# Adafruit_BMP180.net
KiCad netlist of a schematic drawn in EAGLE
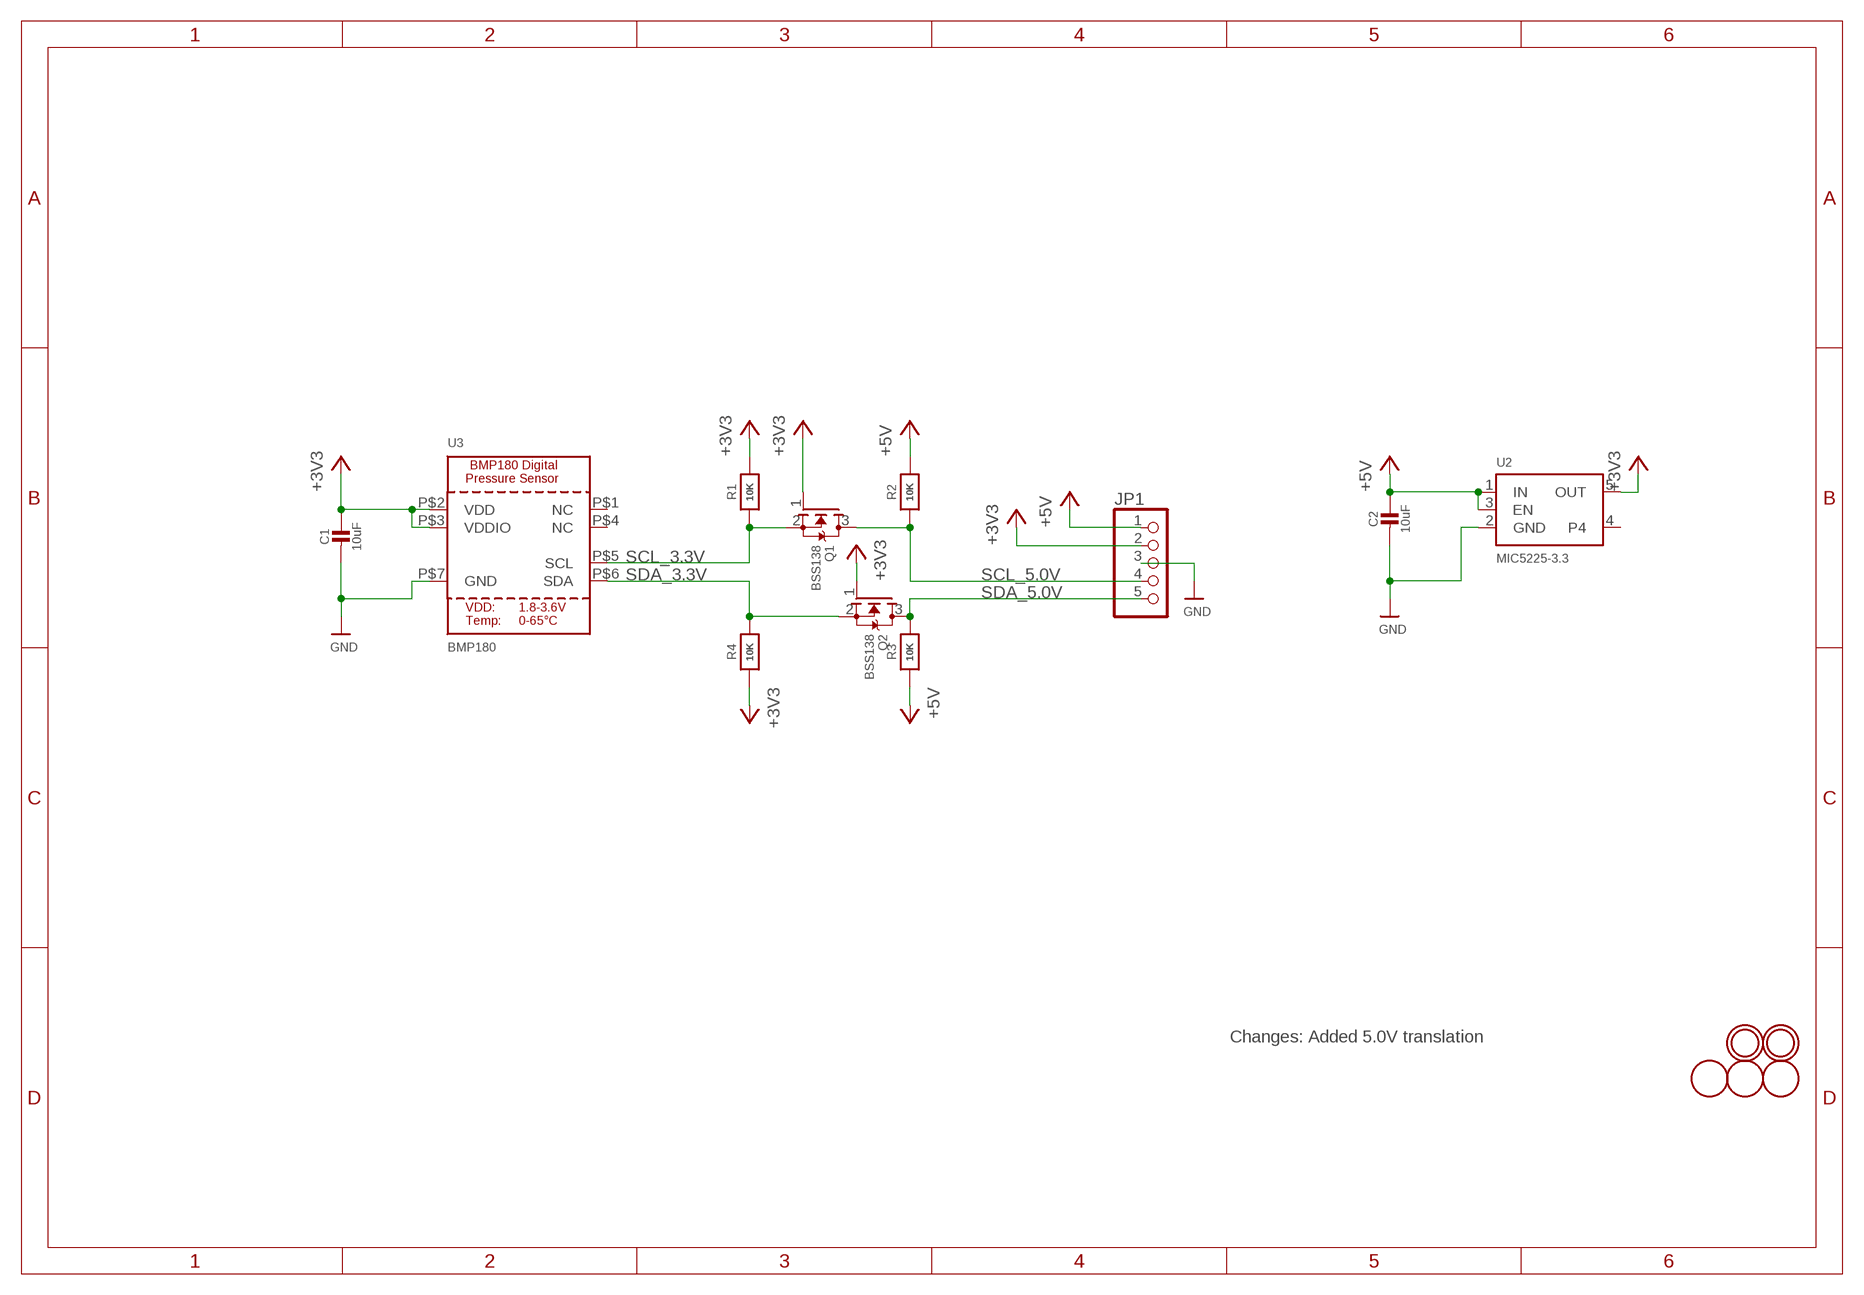
[diagram p0: schematic, sheet 1]

(export (version "E")
  (design (tool "Eeschema 10.0.6"))
  (components
    (comp (ref "C1")
      (value "10uF")
      (footprint "eagle-import:0805-NO")
      (libsource (lib "eagle-import") (part "CAP_CERAMIC0805-NOOUTLINE"))
    )
    (comp (ref "C2")
      (value "10uF")
      (footprint "eagle-import:0805-NO")
      (libsource (lib "eagle-import") (part "CAP_CERAMIC0805-NOOUTLINE"))
    )
    (comp (ref "JP1")
      (value "HEADER-1X570MIL")
      (footprint "eagle-import:1X05_ROUND_70")
      (libsource (lib "eagle-import") (part "HEADER-1X570MIL"))
    )
    (comp (ref "Q1")
      (value "BSS138")
      (footprint "eagle-import:SOT23")
      (libsource (lib "eagle-import") (part "MOSFET-NREFLOW"))
    )
    (comp (ref "Q2")
      (value "BSS138")
      (footprint "eagle-import:SOT23")
      (libsource (lib "eagle-import") (part "MOSFET-NREFLOW"))
    )
    (comp (ref "R1")
      (value "10K")
      (footprint "eagle-import:0805-NO")
      (libsource (lib "eagle-import") (part "RESISTOR0805_NOOUTLINE"))
    )
    (comp (ref "R2")
      (value "10K")
      (footprint "eagle-import:_0805MP")
      (libsource (lib "eagle-import") (part "RESISTOR_0805MP"))
    )
    (comp (ref "R3")
      (value "10K")
      (footprint "eagle-import:0805-NO")
      (libsource (lib "eagle-import") (part "RESISTOR0805_NOOUTLINE"))
    )
    (comp (ref "R4")
      (value "10K")
      (footprint "eagle-import:0805-NO")
      (libsource (lib "eagle-import") (part "RESISTOR0805_NOOUTLINE"))
    )
    (comp (ref "U$1")
      (value "FIDUCIAL")
      (footprint "eagle-import:FIDUCIAL_1MM")
      (libsource (lib "eagle-import") (part "FIDUCIAL"))
    )
    (comp (ref "U$5")
      (value "FIDUCIAL")
      (footprint "eagle-import:FIDUCIAL_1MM")
      (libsource (lib "eagle-import") (part "FIDUCIAL"))
    )
    (comp (ref "U$7")
      (value "MOUNTINGHOLE2.0")
      (footprint "eagle-import:MOUNTINGHOLE_2.0_PLATED")
      (libsource (lib "eagle-import") (part "MOUNTINGHOLE2.0"))
    )
    (comp (ref "U$8")
      (value "MOUNTINGHOLE2.0")
      (footprint "eagle-import:MOUNTINGHOLE_2.0_PLATED")
      (libsource (lib "eagle-import") (part "MOUNTINGHOLE2.0"))
    )
    (comp (ref "U$15")
      (value "FIDUCIAL")
      (footprint "eagle-import:FIDUCIAL_1MM")
      (libsource (lib "eagle-import") (part "FIDUCIAL"))
    )
    (comp (ref "U2")
      (value "MIC5225-3.3")
      (footprint "eagle-import:SOT23-5")
      (libsource (lib "eagle-import") (part "VREG_SOT23-5"))
    )
    (comp (ref "U3")
      (value "BMP180")
      (footprint "eagle-import:BMP180_EXTENDED")
      (libsource (lib "eagle-import") (part "BMP180EXT"))
    )
  )
  (nets
    (net (code "1") (name "+3V3") (class "Default")
      (node (ref "C1") (pin "1") (pinfunction "1_1") (pintype "passive"))
      (node (ref "JP1") (pin "2") (pinfunction "2_2") (pintype "passive"))
      (node (ref "Q1") (pin "1") (pinfunction "G_1") (pintype "bidirectional"))
      (node (ref "Q2") (pin "1") (pinfunction "G_1") (pintype "bidirectional"))
      (node (ref "R1") (pin "2") (pinfunction "2_2") (pintype "passive"))
      (node (ref "R4") (pin "1") (pinfunction "1_1") (pintype "passive"))
      (node (ref "U2") (pin "5") (pinfunction "OUT_5") (pintype "power_in"))
      (node (ref "U3") (pin "P$2") (pinfunction "VDD_P$2") (pintype "power_in"))
      (node (ref "U3") (pin "P$3") (pinfunction "VDDIO_P$3") (pintype "power_in"))
    )
    (net (code "2") (name "+5V") (class "Default")
      (node (ref "C2") (pin "1") (pinfunction "1_1") (pintype "passive"))
      (node (ref "JP1") (pin "1") (pinfunction "1_1") (pintype "passive"))
      (node (ref "R2") (pin "2") (pinfunction "2_2") (pintype "passive"))
      (node (ref "R3") (pin "1") (pinfunction "1_1") (pintype "passive"))
      (node (ref "U2") (pin "1") (pinfunction "IN_1") (pintype "power_in"))
      (node (ref "U2") (pin "3") (pinfunction "EN_3") (pintype "input"))
    )
    (net (code "3") (name "/SCL_3.3V") (class "Default")
      (node (ref "Q1") (pin "2") (pinfunction "S_2") (pintype "bidirectional"))
      (node (ref "R1") (pin "1") (pinfunction "1_1") (pintype "passive"))
      (node (ref "U3") (pin "P$5") (pinfunction "SCL_P$5") (pintype "bidirectional"))
    )
    (net (code "4") (name "/SCL_5.0V") (class "Default")
      (node (ref "JP1") (pin "4") (pinfunction "4_4") (pintype "passive"))
      (node (ref "Q1") (pin "3") (pinfunction "D_3") (pintype "bidirectional"))
      (node (ref "R2") (pin "1") (pinfunction "1_1") (pintype "passive"))
    )
    (net (code "5") (name "/SDA_3.3V") (class "Default")
      (node (ref "Q2") (pin "2") (pinfunction "S_2") (pintype "bidirectional"))
      (node (ref "R4") (pin "2") (pinfunction "2_2") (pintype "passive"))
      (node (ref "U3") (pin "P$6") (pinfunction "SDA_P$6") (pintype "bidirectional"))
    )
    (net (code "6") (name "/SDA_5.0V") (class "Default")
      (node (ref "JP1") (pin "5") (pinfunction "5_5") (pintype "passive"))
      (node (ref "Q2") (pin "3") (pinfunction "D_3") (pintype "bidirectional"))
      (node (ref "R3") (pin "2") (pinfunction "2_2") (pintype "passive"))
    )
    (net (code "7") (name "GND") (class "Default")
      (node (ref "C1") (pin "2") (pinfunction "2_2") (pintype "passive"))
      (node (ref "C2") (pin "2") (pinfunction "2_2") (pintype "passive"))
      (node (ref "JP1") (pin "3") (pinfunction "3_3") (pintype "passive"))
      (node (ref "U2") (pin "2") (pinfunction "GND_2") (pintype "power_in"))
      (node (ref "U3") (pin "P$7") (pinfunction "GND_P$7") (pintype "power_in"))
    )
    (net (code "8") (name "unconnected-(U2-P4-Pad4)") (class "Default")
      (node (ref "U2") (pin "4") (pinfunction "P4_4") (pintype "bidirectional"))
    )
    (net (code "9") (name "unconnected-(U3-NC-PadP$1)") (class "Default")
      (node (ref "U3") (pin "P$1") (pinfunction "NC_P$1") (pintype "no_connect"))
    )
    (net (code "10") (name "unconnected-(U3-NC-PadP$4)") (class "Default")
      (node (ref "U3") (pin "P$4") (pinfunction "NC_P$4") (pintype "no_connect"))
    )
  )
)
